# Driver.net
KiCad netlist of a schematic drawn in EAGLE
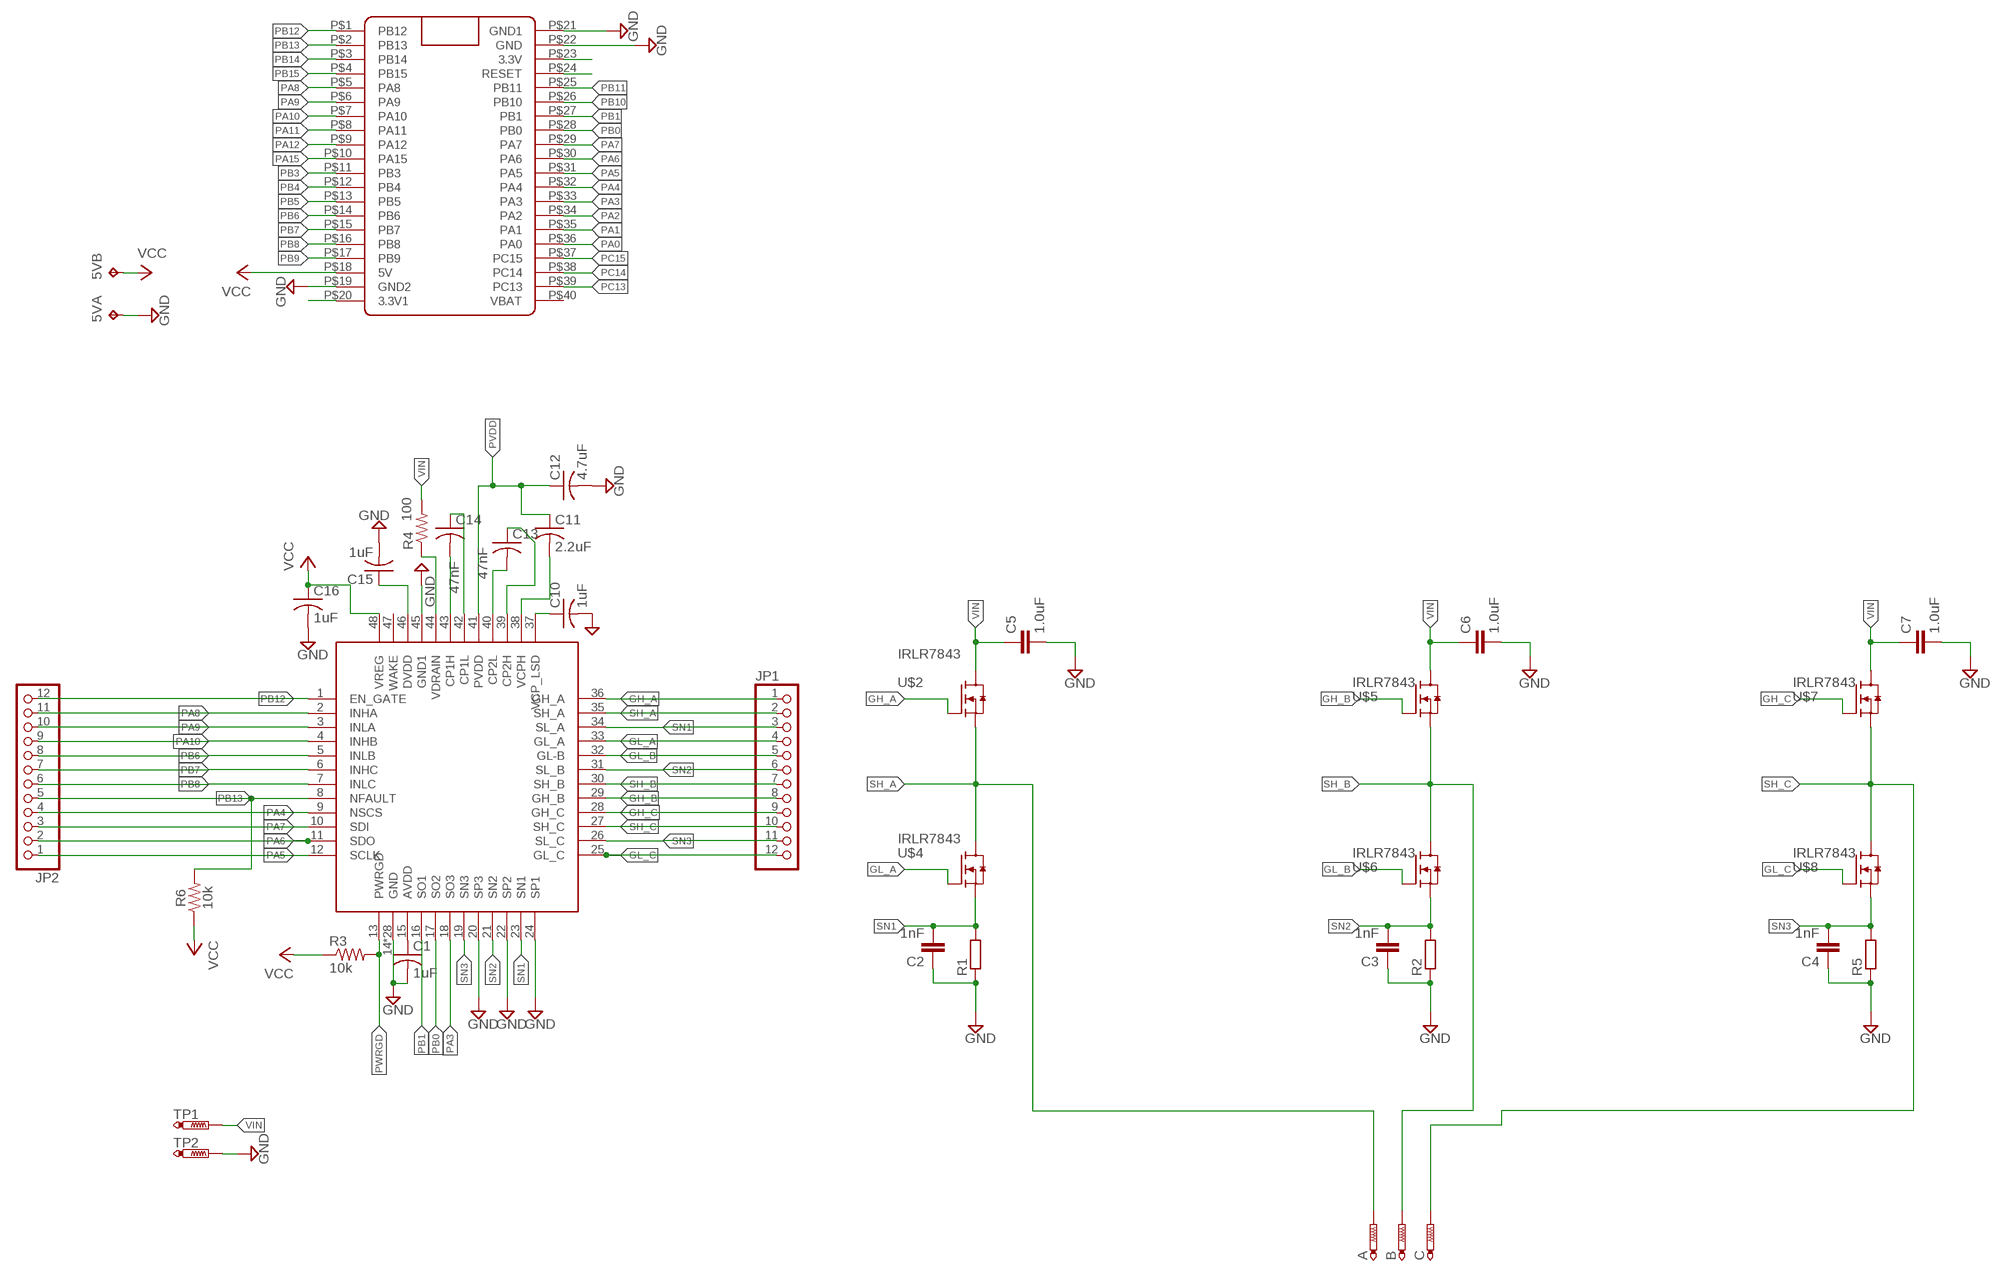
[diagram p0: schematic, sheet 1]

(export (version "E")
  (design (tool "Eeschema 10.0.6"))
  (components
    (comp (ref "5V")
      (value "TP2P2-38-17")
      (footprint "eagle-import:P2-38-17")
      (libsource (lib "eagle-import") (part "TP2P2-38-17"))
    )
    (comp (ref "A")
      (value "PTR1PAD1-20Y")
      (footprint "eagle-import:P1-20Y")
      (libsource (lib "eagle-import") (part "PTR1PAD1-20Y"))
    )
    (comp (ref "B")
      (value "PTR1PAD1-20Y")
      (footprint "eagle-import:P1-20Y")
      (libsource (lib "eagle-import") (part "PTR1PAD1-20Y"))
    )
    (comp (ref "C")
      (value "PTR1PAD1-20Y")
      (footprint "eagle-import:P1-20Y")
      (libsource (lib "eagle-import") (part "PTR1PAD1-20Y"))
    )
    (comp (ref "C1")
      (value "1uF")
      (footprint "eagle-import:C0603")
      (libsource (lib "eagle-import") (part "C-USC0603"))
    )
    (comp (ref "C2")
      (value "1nF")
      (footprint "eagle-import:0603")
      (libsource (lib "eagle-import") (part "1.0NF/1000PF-0603-50V-10%"))
    )
    (comp (ref "C3")
      (value "1nF")
      (footprint "eagle-import:0603")
      (libsource (lib "eagle-import") (part "1.0NF/1000PF-0603-50V-10%"))
    )
    (comp (ref "C4")
      (value "1nF")
      (footprint "eagle-import:0603")
      (libsource (lib "eagle-import") (part "1.0NF/1000PF-0603-50V-10%"))
    )
    (comp (ref "C5")
      (value "1.0uF")
      (footprint "eagle-import:0603")
      (libsource (lib "eagle-import") (part "1.0UF-0603-16V-10%-X7R"))
    )
    (comp (ref "C6")
      (value "1.0uF")
      (footprint "eagle-import:0603")
      (libsource (lib "eagle-import") (part "1.0UF-0603-16V-10%-X7R"))
    )
    (comp (ref "C7")
      (value "1.0uF")
      (footprint "eagle-import:0603")
      (libsource (lib "eagle-import") (part "1.0UF-0603-16V-10%-X7R"))
    )
    (comp (ref "C10")
      (value "1uF")
      (footprint "eagle-import:C0603")
      (libsource (lib "eagle-import") (part "C-USC0603"))
    )
    (comp (ref "C11")
      (value "2.2uF")
      (footprint "eagle-import:C0603")
      (libsource (lib "eagle-import") (part "C-USC0603"))
    )
    (comp (ref "C12")
      (value "4.7uF")
      (footprint "eagle-import:C0603")
      (libsource (lib "eagle-import") (part "C-USC0603"))
    )
    (comp (ref "C13")
      (value "47nF")
      (footprint "eagle-import:C0603")
      (libsource (lib "eagle-import") (part "C-USC0603"))
    )
    (comp (ref "C14")
      (value "47nF")
      (footprint "eagle-import:C0603")
      (libsource (lib "eagle-import") (part "C-USC0603"))
    )
    (comp (ref "C15")
      (value "1uF")
      (footprint "eagle-import:C0603")
      (libsource (lib "eagle-import") (part "C-USC0603"))
    )
    (comp (ref "C16")
      (value "1uF")
      (footprint "eagle-import:C0603")
      (libsource (lib "eagle-import") (part "C-USC0603"))
    )
    (comp (ref "JP1")
      (value "PINHD-1X12")
      (footprint "eagle-import:1X12")
      (libsource (lib "eagle-import") (part "PINHD-1X12"))
    )
    (comp (ref "JP2")
      (value "PINHD-1X12")
      (footprint "eagle-import:1X12")
      (libsource (lib "eagle-import") (part "PINHD-1X12"))
    )
    (comp (ref "R1")
      (value "R-EU_R2512")
      (footprint "eagle-import:R2512")
      (libsource (lib "eagle-import") (part "R-EU_R2512"))
    )
    (comp (ref "R2")
      (value "R-EU_R2512")
      (footprint "eagle-import:R2512")
      (libsource (lib "eagle-import") (part "R-EU_R2512"))
    )
    (comp (ref "R3")
      (value "10k")
      (footprint "eagle-import:R0603")
      (libsource (lib "eagle-import") (part "R-US_R0603"))
    )
    (comp (ref "R4")
      (value "100")
      (footprint "eagle-import:R0603")
      (libsource (lib "eagle-import") (part "R-US_R0603"))
    )
    (comp (ref "R5")
      (value "R-EU_R2512")
      (footprint "eagle-import:R2512")
      (libsource (lib "eagle-import") (part "R-EU_R2512"))
    )
    (comp (ref "R6")
      (value "10k")
      (footprint "eagle-import:0603")
      (libsource (lib "eagle-import") (part "10KOHM-0603-1/10W-1%"))
    )
    (comp (ref "TP1")
      (value "PTR1PAD1-20Y")
      (footprint "eagle-import:P1-20Y")
      (libsource (lib "eagle-import") (part "PTR1PAD1-20Y"))
    )
    (comp (ref "TP2")
      (value "PTR1PAD1-20Y")
      (footprint "eagle-import:P1-20Y")
      (libsource (lib "eagle-import") (part "PTR1PAD1-20Y"))
    )
    (comp (ref "U$1")
      (value "BLUE_PILLADVANCED")
      (footprint "eagle-import:BLUE_PILL_ADV")
      (libsource (lib "eagle-import") (part "BLUE_PILLADVANCED"))
    )
    (comp (ref "U$2")
      (value "IRLR7843")
      (footprint "eagle-import:TO252")
      (libsource (lib "eagle-import") (part "IRLR7843"))
    )
    (comp (ref "U$3")
      (value "DRV8305")
      (footprint "eagle-import:PFB_S-PQFP-G48")
      (libsource (lib "eagle-import") (part "DRV8305"))
    )
    (comp (ref "U$4")
      (value "IRLR7843")
      (footprint "eagle-import:TO252")
      (libsource (lib "eagle-import") (part "IRLR7843"))
    )
    (comp (ref "U$5")
      (value "IRLR7843")
      (footprint "eagle-import:TO252")
      (libsource (lib "eagle-import") (part "IRLR7843"))
    )
    (comp (ref "U$6")
      (value "IRLR7843")
      (footprint "eagle-import:TO252")
      (libsource (lib "eagle-import") (part "IRLR7843"))
    )
    (comp (ref "U$7")
      (value "IRLR7843")
      (footprint "eagle-import:TO252")
      (libsource (lib "eagle-import") (part "IRLR7843"))
    )
    (comp (ref "U$8")
      (value "IRLR7843")
      (footprint "eagle-import:TO252")
      (libsource (lib "eagle-import") (part "IRLR7843"))
    )
  )
  (nets
    (net (code "1") (name "GH_A") (class "Default")
      (node (ref "JP1") (pin "1") (pinfunction "1_1") (pintype "passive"))
      (node (ref "U$2") (pin "1") (pinfunction "G_1") (pintype "passive"))
      (node (ref "U$3") (pin "36") (pinfunction "GH_A_36") (pintype "bidirectional"))
    )
    (net (code "2") (name "GH_B") (class "Default")
      (node (ref "JP1") (pin "8") (pinfunction "8_8") (pintype "passive"))
      (node (ref "U$3") (pin "29") (pinfunction "GH_B_29") (pintype "bidirectional"))
      (node (ref "U$5") (pin "1") (pinfunction "G_1") (pintype "passive"))
    )
    (net (code "3") (name "GH_C") (class "Default")
      (node (ref "JP1") (pin "9") (pinfunction "9_9") (pintype "passive"))
      (node (ref "U$3") (pin "28") (pinfunction "GH_C_28") (pintype "bidirectional"))
      (node (ref "U$7") (pin "1") (pinfunction "G_1") (pintype "passive"))
    )
    (net (code "4") (name "GL_A") (class "Default")
      (node (ref "JP1") (pin "4") (pinfunction "4_4") (pintype "passive"))
      (node (ref "U$3") (pin "33") (pinfunction "GL_A_33") (pintype "bidirectional"))
      (node (ref "U$4") (pin "1") (pinfunction "G_1") (pintype "passive"))
    )
    (net (code "5") (name "GL_B") (class "Default")
      (node (ref "JP1") (pin "5") (pinfunction "5_5") (pintype "passive"))
      (node (ref "U$3") (pin "32") (pinfunction "GL-B_32") (pintype "bidirectional"))
      (node (ref "U$6") (pin "1") (pinfunction "G_1") (pintype "passive"))
    )
    (net (code "6") (name "GL_C") (class "Default")
      (node (ref "JP1") (pin "12") (pinfunction "12_12") (pintype "passive"))
      (node (ref "U$3") (pin "25") (pinfunction "GL_C_25") (pintype "bidirectional"))
      (node (ref "U$8") (pin "1") (pinfunction "G_1") (pintype "passive"))
    )
    (net (code "7") (name "GND") (class "Default")
      (node (ref "5V") (pin "TP-1") (pinfunction "TP_TP-1") (pintype "input"))
      (node (ref "C1") (pin "2") (pinfunction "2_2") (pintype "passive"))
      (node (ref "C10") (pin "2") (pinfunction "2_2") (pintype "passive"))
      (node (ref "C12") (pin "2") (pinfunction "2_2") (pintype "passive"))
      (node (ref "C15") (pin "2") (pinfunction "2_2") (pintype "passive"))
      (node (ref "C16") (pin "2") (pinfunction "2_2") (pintype "passive"))
      (node (ref "C2") (pin "1") (pinfunction "1_1") (pintype "passive"))
      (node (ref "C3") (pin "1") (pinfunction "1_1") (pintype "passive"))
      (node (ref "C4") (pin "1") (pinfunction "1_1") (pintype "passive"))
      (node (ref "C5") (pin "2") (pinfunction "2_2") (pintype "passive"))
      (node (ref "C6") (pin "2") (pinfunction "2_2") (pintype "passive"))
      (node (ref "C7") (pin "2") (pinfunction "2_2") (pintype "passive"))
      (node (ref "R1") (pin "1") (pinfunction "1_1") (pintype "passive"))
      (node (ref "R2") (pin "1") (pinfunction "1_1") (pintype "passive"))
      (node (ref "R5") (pin "1") (pinfunction "1_1") (pintype "passive"))
      (node (ref "TP2") (pin "TP") (pinfunction "TP_TP") (pintype "input"))
      (node (ref "U$1") (pin "P$19") (pinfunction "GND2_P$19") (pintype "bidirectional"))
      (node (ref "U$1") (pin "P$21") (pinfunction "GND1_P$21") (pintype "power_in"))
      (node (ref "U$1") (pin "P$22") (pinfunction "GND_P$22") (pintype "bidirectional"))
      (node (ref "U$3") (pin "14") (pinfunction "GND_14") (pintype "bidirectional"))
      (node (ref "U$3") (pin "20") (pinfunction "SP3_20") (pintype "bidirectional"))
      (node (ref "U$3") (pin "22") (pinfunction "SP2_22") (pintype "bidirectional"))
      (node (ref "U$3") (pin "24") (pinfunction "SP1_24") (pintype "bidirectional"))
      (node (ref "U$3") (pin "45") (pinfunction "GND1_45") (pintype "bidirectional"))
      (node (ref "U$3") (pin "P$1") (pinfunction "GND_P$1") (pintype "bidirectional"))
      (node (ref "U$3") (pin "P$10") (pinfunction "GND_P$10") (pintype "bidirectional"))
      (node (ref "U$3") (pin "P$11") (pinfunction "GND_P$11") (pintype "bidirectional"))
      (node (ref "U$3") (pin "P$12") (pinfunction "GND_P$12") (pintype "bidirectional"))
      (node (ref "U$3") (pin "P$13") (pinfunction "GND_P$13") (pintype "bidirectional"))
      (node (ref "U$3") (pin "P$14") (pinfunction "GND_P$14") (pintype "bidirectional"))
      (node (ref "U$3") (pin "P$15") (pinfunction "GND_P$15") (pintype "bidirectional"))
      (node (ref "U$3") (pin "P$16") (pinfunction "GND_P$16") (pintype "bidirectional"))
      (node (ref "U$3") (pin "P$17") (pinfunction "GND_P$17") (pintype "bidirectional"))
      (node (ref "U$3") (pin "P$18") (pinfunction "GND_P$18") (pintype "bidirectional"))
      (node (ref "U$3") (pin "P$19") (pinfunction "GND_P$19") (pintype "bidirectional"))
      (node (ref "U$3") (pin "P$2") (pinfunction "GND_P$2") (pintype "bidirectional"))
      (node (ref "U$3") (pin "P$20") (pinfunction "GND_P$20") (pintype "bidirectional"))
      (node (ref "U$3") (pin "P$21") (pinfunction "GND_P$21") (pintype "bidirectional"))
      (node (ref "U$3") (pin "P$22") (pinfunction "GND_P$22") (pintype "bidirectional"))
      (node (ref "U$3") (pin "P$23") (pinfunction "GND_P$23") (pintype "bidirectional"))
      (node (ref "U$3") (pin "P$24") (pinfunction "GND_P$24") (pintype "bidirectional"))
      (node (ref "U$3") (pin "P$25") (pinfunction "GND_P$25") (pintype "bidirectional"))
      (node (ref "U$3") (pin "P$26") (pinfunction "GND_P$26") (pintype "bidirectional"))
      (node (ref "U$3") (pin "P$27") (pinfunction "GND_P$27") (pintype "bidirectional"))
      (node (ref "U$3") (pin "P$3") (pinfunction "GND_P$3") (pintype "bidirectional"))
      (node (ref "U$3") (pin "P$4") (pinfunction "GND_P$4") (pintype "bidirectional"))
      (node (ref "U$3") (pin "P$5") (pinfunction "GND_P$5") (pintype "bidirectional"))
      (node (ref "U$3") (pin "P$6") (pinfunction "GND_P$6") (pintype "bidirectional"))
      (node (ref "U$3") (pin "P$7") (pinfunction "GND_P$7") (pintype "bidirectional"))
      (node (ref "U$3") (pin "P$8") (pinfunction "GND_P$8") (pintype "bidirectional"))
      (node (ref "U$3") (pin "P$9") (pinfunction "GND_P$9") (pintype "bidirectional"))
    )
    (net (code "8") (name "Net-(U$3-AVDD)") (class "Default")
      (node (ref "C1") (pin "1") (pinfunction "1_1") (pintype "passive"))
      (node (ref "U$3") (pin "15") (pinfunction "AVDD_15") (pintype "bidirectional"))
    )
    (net (code "9") (name "Net-(U$3-CP1H)") (class "Default")
      (node (ref "C14") (pin "2") (pinfunction "2_2") (pintype "passive"))
      (node (ref "U$3") (pin "43") (pinfunction "CP1H_43") (pintype "bidirectional"))
    )
    (net (code "10") (name "Net-(U$3-CP1L)") (class "Default")
      (node (ref "C14") (pin "1") (pinfunction "1_1") (pintype "passive"))
      (node (ref "U$3") (pin "42") (pinfunction "CP1L_42") (pintype "bidirectional"))
    )
    (net (code "11") (name "Net-(U$3-CP2H)") (class "Default")
      (node (ref "C13") (pin "1") (pinfunction "1_1") (pintype "passive"))
      (node (ref "U$3") (pin "39") (pinfunction "CP2H_39") (pintype "bidirectional"))
    )
    (net (code "12") (name "Net-(U$3-CP2L)") (class "Default")
      (node (ref "C13") (pin "2") (pinfunction "2_2") (pintype "passive"))
      (node (ref "U$3") (pin "40") (pinfunction "CP2L_40") (pintype "bidirectional"))
    )
    (net (code "13") (name "Net-(U$3-DVDD)") (class "Default")
      (node (ref "C15") (pin "1") (pinfunction "1_1") (pintype "passive"))
      (node (ref "U$3") (pin "46") (pinfunction "DVDD_46") (pintype "bidirectional"))
    )
    (net (code "14") (name "Net-(U$3-VCPH)") (class "Default")
      (node (ref "C11") (pin "2") (pinfunction "2_2") (pintype "passive"))
      (node (ref "U$3") (pin "38") (pinfunction "VCPH_38") (pintype "bidirectional"))
    )
    (net (code "15") (name "Net-(U$3-VCP_LSD)") (class "Default")
      (node (ref "C10") (pin "1") (pinfunction "1_1") (pintype "passive"))
      (node (ref "U$3") (pin "37") (pinfunction "VCP_LSD_37") (pintype "bidirectional"))
    )
    (net (code "16") (name "Net-(U$3-VDRAIN)") (class "Default")
      (node (ref "R4") (pin "1") (pinfunction "1_1") (pintype "passive"))
      (node (ref "U$3") (pin "44") (pinfunction "VDRAIN_44") (pintype "bidirectional"))
    )
    (net (code "17") (name "PA0") (class "Default")
      (node (ref "U$1") (pin "P$36") (pinfunction "PA0_P$36") (pintype "bidirectional"))
    )
    (net (code "18") (name "PA1") (class "Default")
      (node (ref "U$1") (pin "P$35") (pinfunction "PA1_P$35") (pintype "bidirectional"))
    )
    (net (code "19") (name "PA2") (class "Default")
      (node (ref "U$1") (pin "P$34") (pinfunction "PA2_P$34") (pintype "bidirectional"))
    )
    (net (code "20") (name "PA3") (class "Default")
      (node (ref "U$1") (pin "P$33") (pinfunction "PA3_P$33") (pintype "bidirectional"))
      (node (ref "U$3") (pin "18") (pinfunction "SO3_18") (pintype "bidirectional"))
    )
    (net (code "21") (name "PA4") (class "Default")
      (node (ref "JP2") (pin "4") (pinfunction "4_4") (pintype "passive"))
      (node (ref "U$1") (pin "P$32") (pinfunction "PA4_P$32") (pintype "bidirectional"))
      (node (ref "U$3") (pin "9") (pinfunction "NSCS_9") (pintype "bidirectional"))
    )
    (net (code "22") (name "PA5") (class "Default")
      (node (ref "JP2") (pin "1") (pinfunction "1_1") (pintype "passive"))
      (node (ref "U$1") (pin "P$31") (pinfunction "PA5_P$31") (pintype "bidirectional"))
      (node (ref "U$3") (pin "12") (pinfunction "SCLK_12") (pintype "bidirectional"))
    )
    (net (code "23") (name "PA6") (class "Default")
      (node (ref "JP2") (pin "2") (pinfunction "2_2") (pintype "passive"))
      (node (ref "U$1") (pin "P$30") (pinfunction "PA6_P$30") (pintype "bidirectional"))
      (node (ref "U$3") (pin "11") (pinfunction "SDO_11") (pintype "bidirectional"))
    )
    (net (code "24") (name "PA7") (class "Default")
      (node (ref "JP2") (pin "3") (pinfunction "3_3") (pintype "passive"))
      (node (ref "U$1") (pin "P$29") (pinfunction "PA7_P$29") (pintype "bidirectional"))
      (node (ref "U$3") (pin "10") (pinfunction "SDI_10") (pintype "bidirectional"))
    )
    (net (code "25") (name "PA8") (class "Default")
      (node (ref "JP2") (pin "11") (pinfunction "11_11") (pintype "passive"))
      (node (ref "U$1") (pin "P$5") (pinfunction "PA8_P$5") (pintype "bidirectional"))
      (node (ref "U$3") (pin "2") (pinfunction "INHA_2") (pintype "bidirectional"))
    )
    (net (code "26") (name "PA9") (class "Default")
      (node (ref "JP2") (pin "10") (pinfunction "10_10") (pintype "passive"))
      (node (ref "U$1") (pin "P$6") (pinfunction "PA9_P$6") (pintype "bidirectional"))
      (node (ref "U$3") (pin "3") (pinfunction "INLA_3") (pintype "bidirectional"))
    )
    (net (code "27") (name "PA10") (class "Default")
      (node (ref "JP2") (pin "9") (pinfunction "9_9") (pintype "passive"))
      (node (ref "U$1") (pin "P$7") (pinfunction "PA10_P$7") (pintype "bidirectional"))
      (node (ref "U$3") (pin "4") (pinfunction "INHB_4") (pintype "bidirectional"))
    )
    (net (code "28") (name "PA11") (class "Default")
      (node (ref "U$1") (pin "P$8") (pinfunction "PA11_P$8") (pintype "bidirectional"))
    )
    (net (code "29") (name "PA12") (class "Default")
      (node (ref "U$1") (pin "P$9") (pinfunction "PA12_P$9") (pintype "bidirectional"))
    )
    (net (code "30") (name "PA15") (class "Default")
      (node (ref "U$1") (pin "P$10") (pinfunction "PA15_P$10") (pintype "bidirectional"))
    )
    (net (code "31") (name "PB0") (class "Default")
      (node (ref "U$1") (pin "P$28") (pinfunction "PB0_P$28") (pintype "bidirectional"))
      (node (ref "U$3") (pin "17") (pinfunction "SO2_17") (pintype "bidirectional"))
    )
    (net (code "32") (name "PB1") (class "Default")
      (node (ref "U$1") (pin "P$27") (pinfunction "PB1_P$27") (pintype "bidirectional"))
      (node (ref "U$3") (pin "16") (pinfunction "SO1_16") (pintype "bidirectional"))
    )
    (net (code "33") (name "PB3") (class "Default")
      (node (ref "U$1") (pin "P$11") (pinfunction "PB3_P$11") (pintype "bidirectional"))
    )
    (net (code "34") (name "PB4") (class "Default")
      (node (ref "U$1") (pin "P$12") (pinfunction "PB4_P$12") (pintype "bidirectional"))
    )
    (net (code "35") (name "PB5") (class "Default")
      (node (ref "U$1") (pin "P$13") (pinfunction "PB5_P$13") (pintype "bidirectional"))
    )
    (net (code "36") (name "PB6") (class "Default")
      (node (ref "JP2") (pin "8") (pinfunction "8_8") (pintype "passive"))
      (node (ref "U$1") (pin "P$14") (pinfunction "PB6_P$14") (pintype "bidirectional"))
      (node (ref "U$3") (pin "5") (pinfunction "INLB_5") (pintype "bidirectional"))
    )
    (net (code "37") (name "PB7") (class "Default")
      (node (ref "JP2") (pin "7") (pinfunction "7_7") (pintype "passive"))
      (node (ref "U$1") (pin "P$15") (pinfunction "PB7_P$15") (pintype "bidirectional"))
      (node (ref "U$3") (pin "6") (pinfunction "INHC_6") (pintype "bidirectional"))
    )
    (net (code "38") (name "PB8") (class "Default")
      (node (ref "JP2") (pin "6") (pinfunction "6_6") (pintype "passive"))
      (node (ref "U$1") (pin "P$16") (pinfunction "PB8_P$16") (pintype "bidirectional"))
      (node (ref "U$3") (pin "7") (pinfunction "INLC_7") (pintype "bidirectional"))
    )
    (net (code "39") (name "PB9") (class "Default")
      (node (ref "U$1") (pin "P$17") (pinfunction "PB9_P$17") (pintype "bidirectional"))
    )
    (net (code "40") (name "PB10") (class "Default")
      (node (ref "U$1") (pin "P$26") (pinfunction "PB10_P$26") (pintype "bidirectional"))
    )
    (net (code "41") (name "PB11") (class "Default")
      (node (ref "U$1") (pin "P$25") (pinfunction "PB11_P$25") (pintype "bidirectional"))
    )
    (net (code "42") (name "PB12") (class "Default")
      (node (ref "JP2") (pin "12") (pinfunction "12_12") (pintype "passive"))
      (node (ref "U$1") (pin "P$1") (pinfunction "PB12_P$1") (pintype "bidirectional"))
      (node (ref "U$3") (pin "1") (pinfunction "EN_GATE_1") (pintype "bidirectional"))
    )
    (net (code "43") (name "PB13") (class "Default")
      (node (ref "JP2") (pin "5") (pinfunction "5_5") (pintype "passive"))
      (node (ref "R6") (pin "2") (pinfunction "2_2") (pintype "passive"))
      (node (ref "U$1") (pin "P$2") (pinfunction "PB13_P$2") (pintype "bidirectional"))
      (node (ref "U$3") (pin "8") (pinfunction "NFAULT_8") (pintype "bidirectional"))
    )
    (net (code "44") (name "PB14") (class "Default")
      (node (ref "U$1") (pin "P$3") (pinfunction "PB14_P$3") (pintype "bidirectional"))
    )
    (net (code "45") (name "PB15") (class "Default")
      (node (ref "U$1") (pin "P$4") (pinfunction "PB15_P$4") (pintype "bidirectional"))
    )
    (net (code "46") (name "PC13") (class "Default")
      (node (ref "U$1") (pin "P$39") (pinfunction "PC13_P$39") (pintype "bidirectional"))
    )
    (net (code "47") (name "PC14") (class "Default")
      (node (ref "U$1") (pin "P$38") (pinfunction "PC14_P$38") (pintype "bidirectional"))
    )
    (net (code "48") (name "PC15") (class "Default")
      (node (ref "U$1") (pin "P$37") (pinfunction "PC15_P$37") (pintype "bidirectional"))
    )
    (net (code "49") (name "PVDD") (class "Default")
      (node (ref "C11") (pin "1") (pinfunction "1_1") (pintype "passive"))
      (node (ref "C12") (pin "1") (pinfunction "1_1") (pintype "passive"))
      (node (ref "U$3") (pin "41") (pinfunction "PVDD_41") (pintype "bidirectional"))
    )
    (net (code "50") (name "PWRGD") (class "Default")
      (node (ref "R3") (pin "2") (pinfunction "2_2") (pintype "passive"))
      (node (ref "U$3") (pin "13") (pinfunction "PWRGD_13") (pintype "bidirectional"))
    )
    (net (code "51") (name "SH_A") (class "Default")
      (node (ref "A") (pin "TP") (pinfunction "TP_TP") (pintype "input"))
      (node (ref "JP1") (pin "2") (pinfunction "2_2") (pintype "passive"))
      (node (ref "U$2") (pin "2") (pinfunction "S_2") (pintype "passive"))
      (node (ref "U$3") (pin "35") (pinfunction "SH_A_35") (pintype "bidirectional"))
      (node (ref "U$4") (pin "3") (pinfunction "D_3") (pintype "passive"))
    )
    (net (code "52") (name "SH_B") (class "Default")
      (node (ref "B") (pin "TP") (pinfunction "TP_TP") (pintype "input"))
      (node (ref "JP1") (pin "7") (pinfunction "7_7") (pintype "passive"))
      (node (ref "U$3") (pin "30") (pinfunction "SH_B_30") (pintype "bidirectional"))
      (node (ref "U$5") (pin "2") (pinfunction "S_2") (pintype "passive"))
      (node (ref "U$6") (pin "3") (pinfunction "D_3") (pintype "passive"))
    )
    (net (code "53") (name "SH_C") (class "Default")
      (node (ref "C") (pin "TP") (pinfunction "TP_TP") (pintype "input"))
      (node (ref "JP1") (pin "10") (pinfunction "10_10") (pintype "passive"))
      (node (ref "U$3") (pin "27") (pinfunction "SH_C_27") (pintype "bidirectional"))
      (node (ref "U$7") (pin "2") (pinfunction "S_2") (pintype "passive"))
      (node (ref "U$8") (pin "3") (pinfunction "D_3") (pintype "passive"))
    )
    (net (code "54") (name "SN1") (class "Default")
      (node (ref "C2") (pin "2") (pinfunction "2_2") (pintype "passive"))
      (node (ref "JP1") (pin "3") (pinfunction "3_3") (pintype "passive"))
      (node (ref "R1") (pin "2") (pinfunction "2_2") (pintype "passive"))
      (node (ref "U$3") (pin "23") (pinfunction "SN1_23") (pintype "bidirectional"))
      (node (ref "U$3") (pin "34") (pinfunction "SL_A_34") (pintype "bidirectional"))
      (node (ref "U$4") (pin "2") (pinfunction "S_2") (pintype "passive"))
    )
    (net (code "55") (name "SN2") (class "Default")
      (node (ref "C3") (pin "2") (pinfunction "2_2") (pintype "passive"))
      (node (ref "JP1") (pin "6") (pinfunction "6_6") (pintype "passive"))
      (node (ref "R2") (pin "2") (pinfunction "2_2") (pintype "passive"))
      (node (ref "U$3") (pin "21") (pinfunction "SN2_21") (pintype "bidirectional"))
      (node (ref "U$3") (pin "31") (pinfunction "SL_B_31") (pintype "bidirectional"))
      (node (ref "U$6") (pin "2") (pinfunction "S_2") (pintype "passive"))
    )
    (net (code "56") (name "SN3") (class "Default")
      (node (ref "C4") (pin "2") (pinfunction "2_2") (pintype "passive"))
      (node (ref "JP1") (pin "11") (pinfunction "11_11") (pintype "passive"))
      (node (ref "R5") (pin "2") (pinfunction "2_2") (pintype "passive"))
      (node (ref "U$3") (pin "19") (pinfunction "SN3_19") (pintype "bidirectional"))
      (node (ref "U$3") (pin "26") (pinfunction "SL_C_26") (pintype "bidirectional"))
      (node (ref "U$8") (pin "2") (pinfunction "S_2") (pintype "passive"))
    )
    (net (code "57") (name "VCC") (class "Default")
      (node (ref "5V") (pin "TP-2") (pinfunction "TP_TP-2") (pintype "input"))
      (node (ref "C16") (pin "1") (pinfunction "1_1") (pintype "passive"))
      (node (ref "R3") (pin "1") (pinfunction "1_1") (pintype "passive"))
      (node (ref "R6") (pin "1") (pinfunction "1_1") (pintype "passive"))
      (node (ref "U$1") (pin "P$18") (pinfunction "5V_P$18") (pintype "bidirectional"))
      (node (ref "U$3") (pin "48") (pinfunction "VREG_48") (pintype "bidirectional"))
    )
    (net (code "58") (name "VIN") (class "Default")
      (node (ref "C5") (pin "1") (pinfunction "1_1") (pintype "passive"))
      (node (ref "C6") (pin "1") (pinfunction "1_1") (pintype "passive"))
      (node (ref "C7") (pin "1") (pinfunction "1_1") (pintype "passive"))
      (node (ref "R4") (pin "2") (pinfunction "2_2") (pintype "passive"))
      (node (ref "TP1") (pin "TP") (pinfunction "TP_TP") (pintype "input"))
      (node (ref "U$2") (pin "3") (pinfunction "D_3") (pintype "passive"))
      (node (ref "U$5") (pin "3") (pinfunction "D_3") (pintype "passive"))
      (node (ref "U$7") (pin "3") (pinfunction "D_3") (pintype "passive"))
    )
    (net (code "59") (name "unconnected-(U$1-3.3V-PadP$23)") (class "Default")
      (node (ref "U$1") (pin "P$23") (pinfunction "3.3V_P$23") (pintype "bidirectional"))
    )
    (net (code "60") (name "unconnected-(U$1-3.3V1-PadP$20)") (class "Default")
      (node (ref "U$1") (pin "P$20") (pinfunction "3.3V1_P$20") (pintype "bidirectional"))
    )
    (net (code "61") (name "unconnected-(U$1-RESET-PadP$24)") (class "Default")
      (node (ref "U$1") (pin "P$24") (pinfunction "RESET_P$24") (pintype "bidirectional"))
    )
    (net (code "62") (name "unconnected-(U$1-VBAT-PadP$40)") (class "Default")
      (node (ref "U$1") (pin "P$40") (pinfunction "VBAT_P$40") (pintype "bidirectional"))
    )
    (net (code "63") (name "unconnected-(U$3-WAKE-Pad47)") (class "Default")
      (node (ref "U$3") (pin "47") (pinfunction "WAKE_47") (pintype "bidirectional"))
    )
  )
)
